# Peripherals.net
KiCad netlist of a schematic drawn in Altium Designer
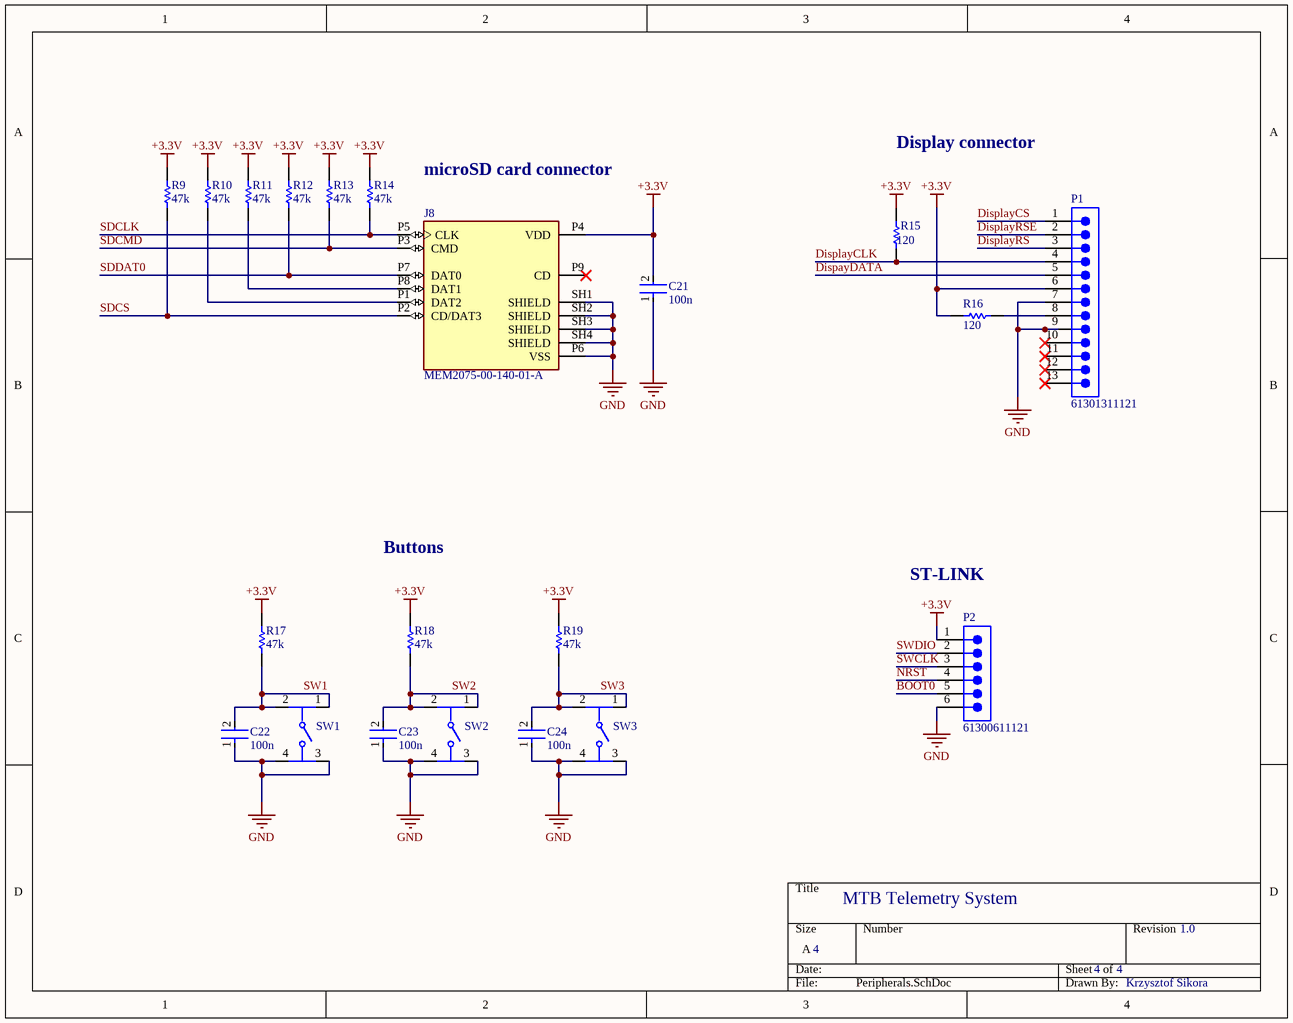
[diagram p0: Peripherals.SchDoc]

(export (version "E")
  (design (tool "Eeschema 10.0.6"))
  (components
    (comp (ref "C21")
      (value "100n")
      (footprint "FP-C0603C-CF-MFG")
      (description "CAP CER 0.1UF 50V X7R 0603")
      (fields (field (name "TOLERANCE") "0.1") (field (name "MANUFACTURER") "KEMET"))
      (libsource (lib "Altium Content Vault") (part "b4654b650e69147ec39a6b967a45e02"))
    )
    (comp (ref "C22")
      (value "100n")
      (footprint "FP-C0603C-CF-MFG")
      (description "CAP CER 0.1UF 50V X7R 0603")
      (fields (field (name "TOLERANCE") "0.1") (field (name "MANUFACTURER") "KEMET"))
      (libsource (lib "Altium Content Vault") (part "b4654b650e69147ec39a6b967a45e02"))
    )
    (comp (ref "C23")
      (value "100n")
      (footprint "FP-C0603C-CF-MFG")
      (description "CAP CER 0.1UF 50V X7R 0603")
      (fields (field (name "TOLERANCE") "0.1") (field (name "MANUFACTURER") "KEMET"))
      (libsource (lib "Altium Content Vault") (part "b4654b650e69147ec39a6b967a45e02"))
    )
    (comp (ref "C24")
      (value "100n")
      (footprint "FP-C0603C-CF-MFG")
      (description "CAP CER 0.1UF 50V X7R 0603")
      (fields (field (name "TOLERANCE") "0.1") (field (name "MANUFACTURER") "KEMET"))
      (libsource (lib "Altium Content Vault") (part "b4654b650e69147ec39a6b967a45e02"))
    )
    (comp (ref "J8")
      (value "MEM2075-00-140-01-A")
      (footprint "GCT_MEM2075-00-140-01-A")
      (description "Micro SD Memory Card Connector, 1.4mm Profile SMT, Push-Push, with Normally open Switch")
      (libsource (lib "MEM2075-00-140-01-A") (part "MEM2075-00-140-01-A"))
    )
    (comp (ref "P1")
      (value "61301311121")
      (footprint "61301311121")
      (libsource (lib "Altium Content Vault") (part "Header_Male_1R_13P"))
    )
    (comp (ref "P2")
      (value "61300611121")
      (footprint "61300611121")
      (libsource (lib "Altium Content Vault") (part "Header_Male_1R_06P"))
    )
    (comp (ref "R9")
      (value "47k")
      (footprint "RESC2013X60X35ML10T20")
      (fields (field (name "TOLERANCE") "5%") (field (name "MANUFACTURER") "Yageo"))
      (libsource (lib "Altium Content Vault") (part "RES-2"))
    )
    (comp (ref "R10")
      (value "47k")
      (footprint "RESC2013X60X35ML10T20")
      (fields (field (name "TOLERANCE") "5%") (field (name "MANUFACTURER") "Yageo"))
      (libsource (lib "Altium Content Vault") (part "RES-2"))
    )
    (comp (ref "R11")
      (value "47k")
      (footprint "RESC2013X60X35ML10T20")
      (fields (field (name "TOLERANCE") "5%") (field (name "MANUFACTURER") "Yageo"))
      (libsource (lib "Altium Content Vault") (part "RES-2"))
    )
    (comp (ref "R12")
      (value "47k")
      (footprint "RESC2013X60X35ML10T20")
      (fields (field (name "TOLERANCE") "5%") (field (name "MANUFACTURER") "Yageo"))
      (libsource (lib "Altium Content Vault") (part "RES-2"))
    )
    (comp (ref "R13")
      (value "47k")
      (footprint "RESC2013X60X35ML10T20")
      (fields (field (name "TOLERANCE") "5%") (field (name "MANUFACTURER") "Yageo"))
      (libsource (lib "Altium Content Vault") (part "RES-2"))
    )
    (comp (ref "R14")
      (value "47k")
      (footprint "RESC2013X60X35ML10T20")
      (fields (field (name "TOLERANCE") "5%") (field (name "MANUFACTURER") "Yageo"))
      (libsource (lib "Altium Content Vault") (part "RES-2"))
    )
    (comp (ref "R15")
      (value "120")
      (footprint "RESC2013X60X35ML10T20")
      (fields (field (name "TOLERANCE") "5%") (field (name "MANUFACTURER") "Yageo"))
      (libsource (lib "Altium Content Vault") (part "RES-2"))
    )
    (comp (ref "R16")
      (value "120")
      (footprint "RESC2013X60X35ML10T20")
      (fields (field (name "TOLERANCE") "5%") (field (name "MANUFACTURER") "Yageo"))
      (libsource (lib "Altium Content Vault") (part "RES-2"))
    )
    (comp (ref "R17")
      (value "47k")
      (footprint "RESC2013X60X35ML10T20")
      (fields (field (name "TOLERANCE") "5%") (field (name "MANUFACTURER") "Yageo"))
      (libsource (lib "Altium Content Vault") (part "RES-2"))
    )
    (comp (ref "R18")
      (value "47k")
      (footprint "RESC2013X60X35ML10T20")
      (fields (field (name "TOLERANCE") "5%") (field (name "MANUFACTURER") "Yageo"))
      (libsource (lib "Altium Content Vault") (part "RES-2"))
    )
    (comp (ref "R19")
      (value "47k")
      (footprint "RESC2013X60X35ML10T20")
      (fields (field (name "TOLERANCE") "5%") (field (name "MANUFACTURER") "Yageo"))
      (libsource (lib "Altium Content Vault") (part "RES-2"))
    )
    (comp (ref "SW1")
      (value "1-1825910-0")
      (footprint "FP-1-1825910-0-MFG")
      (description "SWITCH TACTILE SPST-NO 0.05A 24V")
      (libsource (lib "Altium Content Vault") (part "b8895f3f4cefb76e1819d2863dba89b"))
    )
    (comp (ref "SW2")
      (value "1-1825910-0")
      (footprint "FP-1-1825910-0-MFG")
      (description "SWITCH TACTILE SPST-NO 0.05A 24V")
      (libsource (lib "Altium Content Vault") (part "b8895f3f4cefb76e1819d2863dba89b"))
    )
    (comp (ref "SW3")
      (value "1-1825910-0")
      (footprint "FP-1-1825910-0-MFG")
      (description "SWITCH TACTILE SPST-NO 0.05A 24V")
      (libsource (lib "Altium Content Vault") (part "b8895f3f4cefb76e1819d2863dba89b"))
    )
  )
  (nets
    (net (code "1") (name "+3.3V") (class "Default")
      (node (ref "C21") (pin "2") (pinfunction "2_2") (pintype "passive"))
      (node (ref "J8") (pin "P4") (pinfunction "VDD_P4") (pintype "power_in"))
      (node (ref "P1") (pin "6") (pinfunction "6_6") (pintype "passive"))
      (node (ref "P2") (pin "1") (pinfunction "1_1") (pintype "passive"))
      (node (ref "R10") (pin "2") (pinfunction "2_2") (pintype "passive"))
      (node (ref "R11") (pin "2") (pinfunction "2_2") (pintype "passive"))
      (node (ref "R12") (pin "2") (pinfunction "2_2") (pintype "passive"))
      (node (ref "R13") (pin "2") (pinfunction "2_2") (pintype "passive"))
      (node (ref "R14") (pin "2") (pinfunction "2_2") (pintype "passive"))
      (node (ref "R15") (pin "1") (pinfunction "1_1") (pintype "passive"))
      (node (ref "R16") (pin "2") (pinfunction "2_2") (pintype "passive"))
      (node (ref "R17") (pin "2") (pinfunction "2_2") (pintype "passive"))
      (node (ref "R18") (pin "2") (pinfunction "2_2") (pintype "passive"))
      (node (ref "R19") (pin "2") (pinfunction "2_2") (pintype "passive"))
      (node (ref "R9") (pin "2") (pinfunction "2_2") (pintype "passive"))
    )
    (net (code "2") (name "/BOOT0") (class "Default")
      (node (ref "P2") (pin "5") (pinfunction "5_5") (pintype "passive"))
    )
    (net (code "3") (name "/DispayDATA") (class "Default")
      (node (ref "P1") (pin "5") (pinfunction "5_5") (pintype "passive"))
    )
    (net (code "4") (name "/DisplayCLK") (class "Default")
      (node (ref "P1") (pin "4") (pinfunction "4_4") (pintype "passive"))
      (node (ref "R15") (pin "2") (pinfunction "2_2") (pintype "passive"))
    )
    (net (code "5") (name "/DisplayCS") (class "Default")
      (node (ref "P1") (pin "1") (pinfunction "1_1") (pintype "passive"))
    )
    (net (code "6") (name "/DisplayRS") (class "Default")
      (node (ref "P1") (pin "3") (pinfunction "3_3") (pintype "passive"))
    )
    (net (code "7") (name "/DisplayRSE") (class "Default")
      (node (ref "P1") (pin "2") (pinfunction "2_2") (pintype "passive"))
    )
    (net (code "8") (name "/NRST") (class "Default")
      (node (ref "P2") (pin "4") (pinfunction "4_4") (pintype "passive"))
    )
    (net (code "9") (name "/SDCLK") (class "Default")
      (node (ref "J8") (pin "P5") (pinfunction "CLK_P5") (pintype "bidirectional"))
      (node (ref "R14") (pin "1") (pinfunction "1_1") (pintype "passive"))
    )
    (net (code "10") (name "/SDCMD") (class "Default")
      (node (ref "J8") (pin "P3") (pinfunction "CMD_P3") (pintype "bidirectional"))
      (node (ref "R13") (pin "1") (pinfunction "1_1") (pintype "passive"))
    )
    (net (code "11") (name "/SDCS") (class "Default")
      (node (ref "J8") (pin "P2") (pinfunction "CD/DAT3_P2") (pintype "bidirectional"))
      (node (ref "R9") (pin "1") (pinfunction "1_1") (pintype "passive"))
    )
    (net (code "12") (name "/SDDAT0") (class "Default")
      (node (ref "J8") (pin "P7") (pinfunction "DAT0_P7") (pintype "bidirectional"))
      (node (ref "R12") (pin "1") (pinfunction "1_1") (pintype "passive"))
    )
    (net (code "13") (name "/SW1") (class "Default")
      (node (ref "C22") (pin "2") (pinfunction "2_2") (pintype "passive"))
      (node (ref "R17") (pin "1") (pinfunction "1_1") (pintype "passive"))
      (node (ref "SW1") (pin "1") (pinfunction "1_1") (pintype "passive"))
      (node (ref "SW1") (pin "2") (pinfunction "2_2") (pintype "passive"))
    )
    (net (code "14") (name "/SW2") (class "Default")
      (node (ref "C23") (pin "2") (pinfunction "2_2") (pintype "passive"))
      (node (ref "R18") (pin "1") (pinfunction "1_1") (pintype "passive"))
      (node (ref "SW2") (pin "1") (pinfunction "1_1") (pintype "passive"))
      (node (ref "SW2") (pin "2") (pinfunction "2_2") (pintype "passive"))
    )
    (net (code "15") (name "/SW3") (class "Default")
      (node (ref "C24") (pin "2") (pinfunction "2_2") (pintype "passive"))
      (node (ref "R19") (pin "1") (pinfunction "1_1") (pintype "passive"))
      (node (ref "SW3") (pin "1") (pinfunction "1_1") (pintype "passive"))
      (node (ref "SW3") (pin "2") (pinfunction "2_2") (pintype "passive"))
    )
    (net (code "16") (name "/SWCLK") (class "Default")
      (node (ref "P2") (pin "3") (pinfunction "3_3") (pintype "passive"))
    )
    (net (code "17") (name "/SWDIO") (class "Default")
      (node (ref "P2") (pin "2") (pinfunction "2_2") (pintype "passive"))
    )
    (net (code "18") (name "GND") (class "Default")
      (node (ref "C21") (pin "1") (pinfunction "1_1") (pintype "passive"))
      (node (ref "C22") (pin "1") (pinfunction "1_1") (pintype "passive"))
      (node (ref "C23") (pin "1") (pinfunction "1_1") (pintype "passive"))
      (node (ref "C24") (pin "1") (pinfunction "1_1") (pintype "passive"))
      (node (ref "J8") (pin "P6") (pinfunction "VSS_P6") (pintype "power_in"))
      (node (ref "J8") (pin "SH1") (pinfunction "SHIELD_SH1") (pintype "power_in"))
      (node (ref "J8") (pin "SH2") (pinfunction "SHIELD_SH2") (pintype "power_in"))
      (node (ref "J8") (pin "SH3") (pinfunction "SHIELD_SH3") (pintype "power_in"))
      (node (ref "J8") (pin "SH4") (pinfunction "SHIELD_SH4") (pintype "power_in"))
      (node (ref "P1") (pin "7") (pinfunction "7_7") (pintype "passive"))
      (node (ref "P1") (pin "9") (pinfunction "9_9") (pintype "passive"))
      (node (ref "P2") (pin "6") (pinfunction "6_6") (pintype "passive"))
      (node (ref "SW1") (pin "3") (pinfunction "3_3") (pintype "passive"))
      (node (ref "SW1") (pin "4") (pinfunction "4_4") (pintype "passive"))
      (node (ref "SW2") (pin "3") (pinfunction "3_3") (pintype "passive"))
      (node (ref "SW2") (pin "4") (pinfunction "4_4") (pintype "passive"))
      (node (ref "SW3") (pin "3") (pinfunction "3_3") (pintype "passive"))
      (node (ref "SW3") (pin "4") (pinfunction "4_4") (pintype "passive"))
    )
    (net (code "19") (name "Net-(J8-DAT1)") (class "Default")
      (node (ref "J8") (pin "P8") (pinfunction "DAT1_P8") (pintype "bidirectional"))
      (node (ref "R11") (pin "1") (pinfunction "1_1") (pintype "passive"))
    )
    (net (code "20") (name "Net-(J8-DAT2)") (class "Default")
      (node (ref "J8") (pin "P1") (pinfunction "DAT2_P1") (pintype "bidirectional"))
      (node (ref "R10") (pin "1") (pinfunction "1_1") (pintype "passive"))
    )
    (net (code "21") (name "Net-(P1-Pad8)") (class "Default")
      (node (ref "P1") (pin "8") (pinfunction "8_8") (pintype "passive"))
      (node (ref "R16") (pin "1") (pinfunction "1_1") (pintype "passive"))
    )
    (net (code "22") (name "unconnected-(J8-CD-PadP9)") (class "Default")
      (node (ref "J8") (pin "P9") (pinfunction "CD_P9") (pintype "passive+no_connect"))
    )
    (net (code "23") (name "unconnected-(P1-Pad10)") (class "Default")
      (node (ref "P1") (pin "10") (pinfunction "10_10") (pintype "passive+no_connect"))
    )
    (net (code "24") (name "unconnected-(P1-Pad11)") (class "Default")
      (node (ref "P1") (pin "11") (pinfunction "11_11") (pintype "passive+no_connect"))
    )
    (net (code "25") (name "unconnected-(P1-Pad12)") (class "Default")
      (node (ref "P1") (pin "12") (pinfunction "12_12") (pintype "passive+no_connect"))
    )
    (net (code "26") (name "unconnected-(P1-Pad13)") (class "Default")
      (node (ref "P1") (pin "13") (pinfunction "13_13") (pintype "passive+no_connect"))
    )
  )
)
